# LPF_ADC.net
KiCad netlist of a schematic drawn in Altium Designer
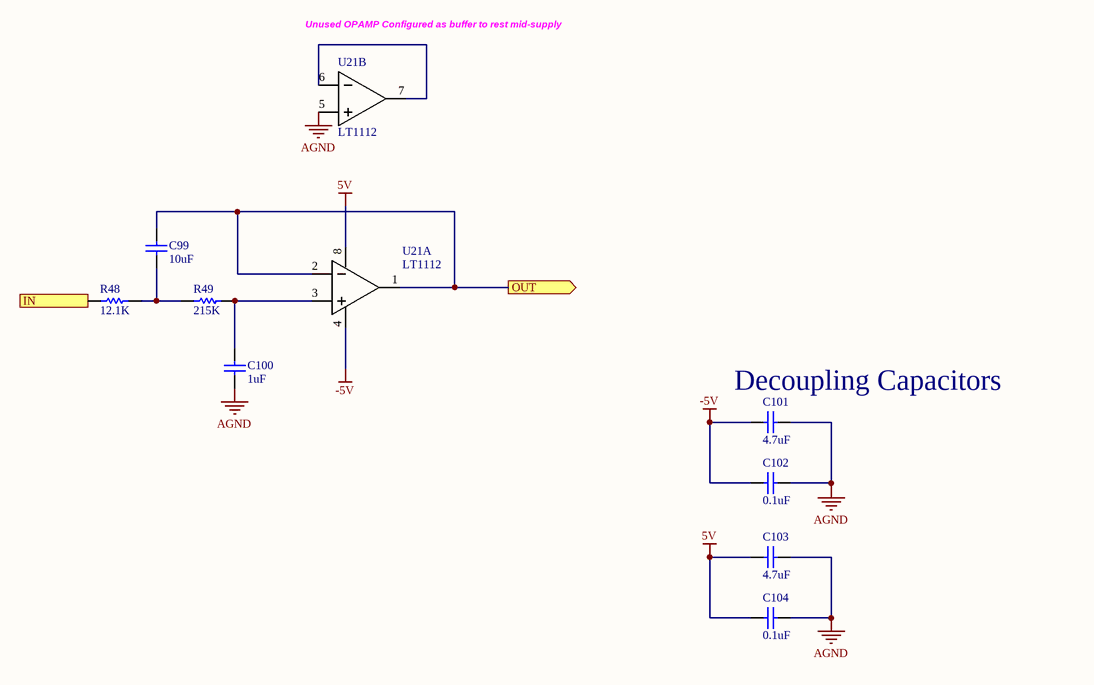
[diagram p0: LPF_ADC.SchDoc]

(export (version "E")
  (design (tool "Eeschema 10.0.6"))
  (components
    (comp (ref "C99")
      (value "10uF")
      (footprint "0402_Cap")
      (description "Capacitor, 16nF, 0805, 25V")
      (libsource (lib "Arturo_Approved") (part "08051C163JAT2A"))
    )
    (comp (ref "C100")
      (value "1uF")
      (footprint "0402_Cap")
      (description "Capacitor, 1.6nF, 0805, 25V")
      (libsource (lib "Arturo_Approved") (part "GRM2165C2A162JA01D"))
    )
    (comp (ref "C101")
      (value "4.7uF")
      (footprint "0402_Cap")
      (description "Capacitor, 4.7uF, 0805")
      (libsource (lib "Arturo_Approved") (part "CL21A475KAQNNNE"))
    )
    (comp (ref "C102")
      (value "0.1uF")
      (footprint "0402_Cap")
      (description "Capacitor, 0.1uF, 0805")
      (libsource (lib "Arturo_Approved") (part "CL21B104KACNNNC"))
    )
    (comp (ref "C103")
      (value "4.7uF")
      (footprint "0402_Cap")
      (description "Capacitor, 4.7uF, 0805")
      (libsource (lib "Arturo_Approved") (part "CL21A475KAQNNNE"))
    )
    (comp (ref "C104")
      (value "0.1uF")
      (footprint "0402_Cap")
      (description "Capacitor, 0.1uF, 0805")
      (libsource (lib "Arturo_Approved") (part "CL21B104KACNNNC"))
    )
    (comp (ref "R48")
      (value "12.1K")
      (footprint "0402_Res")
      (description "1.65k")
      (libsource (lib "Arturo_Approved") (part "RC0805FR-071K65L"))
    )
    (comp (ref "R49")
      (value "215K")
      (footprint "0402_Res")
      (description "5.9k")
      (libsource (lib "Arturo_Approved") (part "RC0805FR-075K9L"))
    )
    (comp (ref "U21")
      (value "LT1112")
      (footprint "SOIC_8")
      (libsource (lib "Arturo_Approved") (part "LT1112"))
    )
  )
  (nets
    (net (code "1") (name "-5V") (class "Default")
      (node (ref "C101") (pin "1") (pinfunction "1_1") (pintype "passive"))
      (node (ref "C102") (pin "1") (pinfunction "1_1") (pintype "passive"))
      (node (ref "U21") (pin "4") (pinfunction "4_4") (pintype "passive"))
    )
    (net (code "2") (name "/IN") (class "Default")
      (node (ref "R48") (pin "1") (pinfunction "1_1") (pintype "passive"))
    )
    (net (code "3") (name "/OUT") (class "Default")
      (node (ref "C99") (pin "2") (pinfunction "2_2") (pintype "passive"))
      (node (ref "U21") (pin "1") (pinfunction "1_1") (pintype "passive"))
      (node (ref "U21") (pin "2") (pinfunction "2_2") (pintype "passive"))
    )
    (net (code "4") (name "5V") (class "Default")
      (node (ref "C103") (pin "1") (pinfunction "1_1") (pintype "passive"))
      (node (ref "C104") (pin "1") (pinfunction "1_1") (pintype "passive"))
      (node (ref "U21") (pin "8") (pinfunction "8_8") (pintype "passive"))
    )
    (net (code "5") (name "AGND") (class "Default")
      (node (ref "C100") (pin "1") (pinfunction "1_1") (pintype "passive"))
      (node (ref "C101") (pin "2") (pinfunction "2_2") (pintype "passive"))
      (node (ref "C102") (pin "2") (pinfunction "2_2") (pintype "passive"))
      (node (ref "C103") (pin "2") (pinfunction "2_2") (pintype "passive"))
      (node (ref "C104") (pin "2") (pinfunction "2_2") (pintype "passive"))
      (node (ref "U21") (pin "5") (pinfunction "5_5") (pintype "passive"))
    )
    (net (code "6") (name "Net-(C99-Pad1)") (class "Default")
      (node (ref "C99") (pin "1") (pinfunction "1_1") (pintype "passive"))
      (node (ref "R48") (pin "2") (pinfunction "2_2") (pintype "passive"))
      (node (ref "R49") (pin "1") (pinfunction "1_1") (pintype "passive"))
    )
    (net (code "7") (name "Net-(C100-Pad2)") (class "Default")
      (node (ref "C100") (pin "2") (pinfunction "2_2") (pintype "passive"))
      (node (ref "R49") (pin "2") (pinfunction "2_2") (pintype "passive"))
      (node (ref "U21") (pin "3") (pinfunction "3_3") (pintype "passive"))
    )
    (net (code "8") (name "Net-(U21-Pad6)") (class "Default")
      (node (ref "U21") (pin "6") (pinfunction "6_6") (pintype "passive"))
      (node (ref "U21") (pin "7") (pinfunction "7_7") (pintype "passive"))
    )
  )
)
